# uMultimeter_ExpProbeB_Sch.net
KiCad netlist of a schematic drawn in Altium Designer
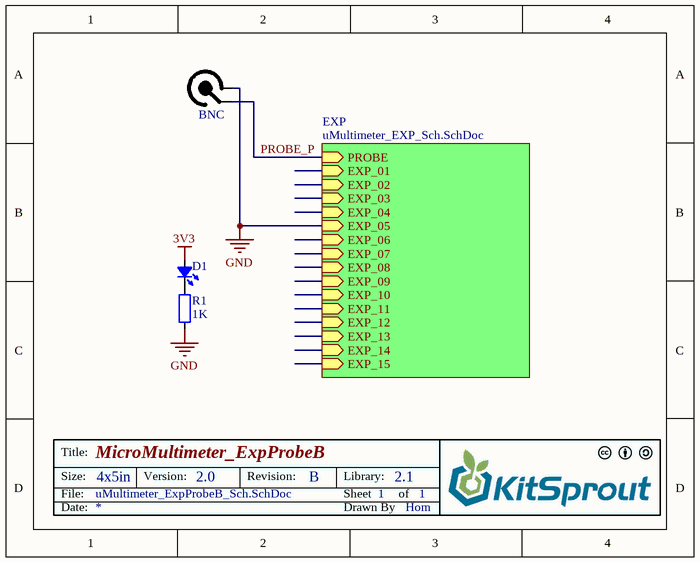
[diagram p0: uMultimeter_ExpProbeB_Sch.SchDoc]

(export (version "E")
  (design (tool "Eeschema 10.0.6"))
  (components
    (comp (ref "BNC")
      (value "BNC")
      (footprint "PCB_ConnectorCable:BNC_4P")
      (libsource (lib "SCH_Connector") (part "BNC"))
    )
    (comp (ref "D1")
      (value "LED_0805")
      (footprint "PCB_ActiveLED:LED_0805_BLUE")
      (description "LED")
      (libsource (lib "SCH_Active") (part "LED_0805"))
    )
    (comp (ref "R1")
      (value "1K")
      (footprint "PCB_PassiveRes:RES_0603")
      (description "Resistor")
      (fields (field (name "Comment") "Res_0603"))
      (libsource (lib "SCH_Passive") (part "Res_0603"))
    )
  )
  (nets
    (net (code "15") (name "/PROBE_P") (class "Default")
      (node (ref "BNC") (pin "1") (pinfunction "1_1") (pintype "passive"))
    )
    (net (code "16") (name "3V3") (class "Default")
      (node (ref "D1") (pin "1") (pinfunction "A_1") (pintype "passive"))
    )
    (net (code "17") (name "GND") (class "Default")
      (node (ref "BNC") (pin "2") (pinfunction "2_2") (pintype "passive"))
      (node (ref "R1") (pin "2") (pinfunction "2_2") (pintype "passive"))
    )
    (net (code "18") (name "Net-(D1-K)") (class "Default")
      (node (ref "D1") (pin "2") (pinfunction "K_2") (pintype "passive"))
      (node (ref "R1") (pin "1") (pinfunction "1_1") (pintype "passive"))
    )
  )
)
